# LHR_Mag_Sensor_Mk2.net
KiCad netlist of a schematic drawn in EAGLE
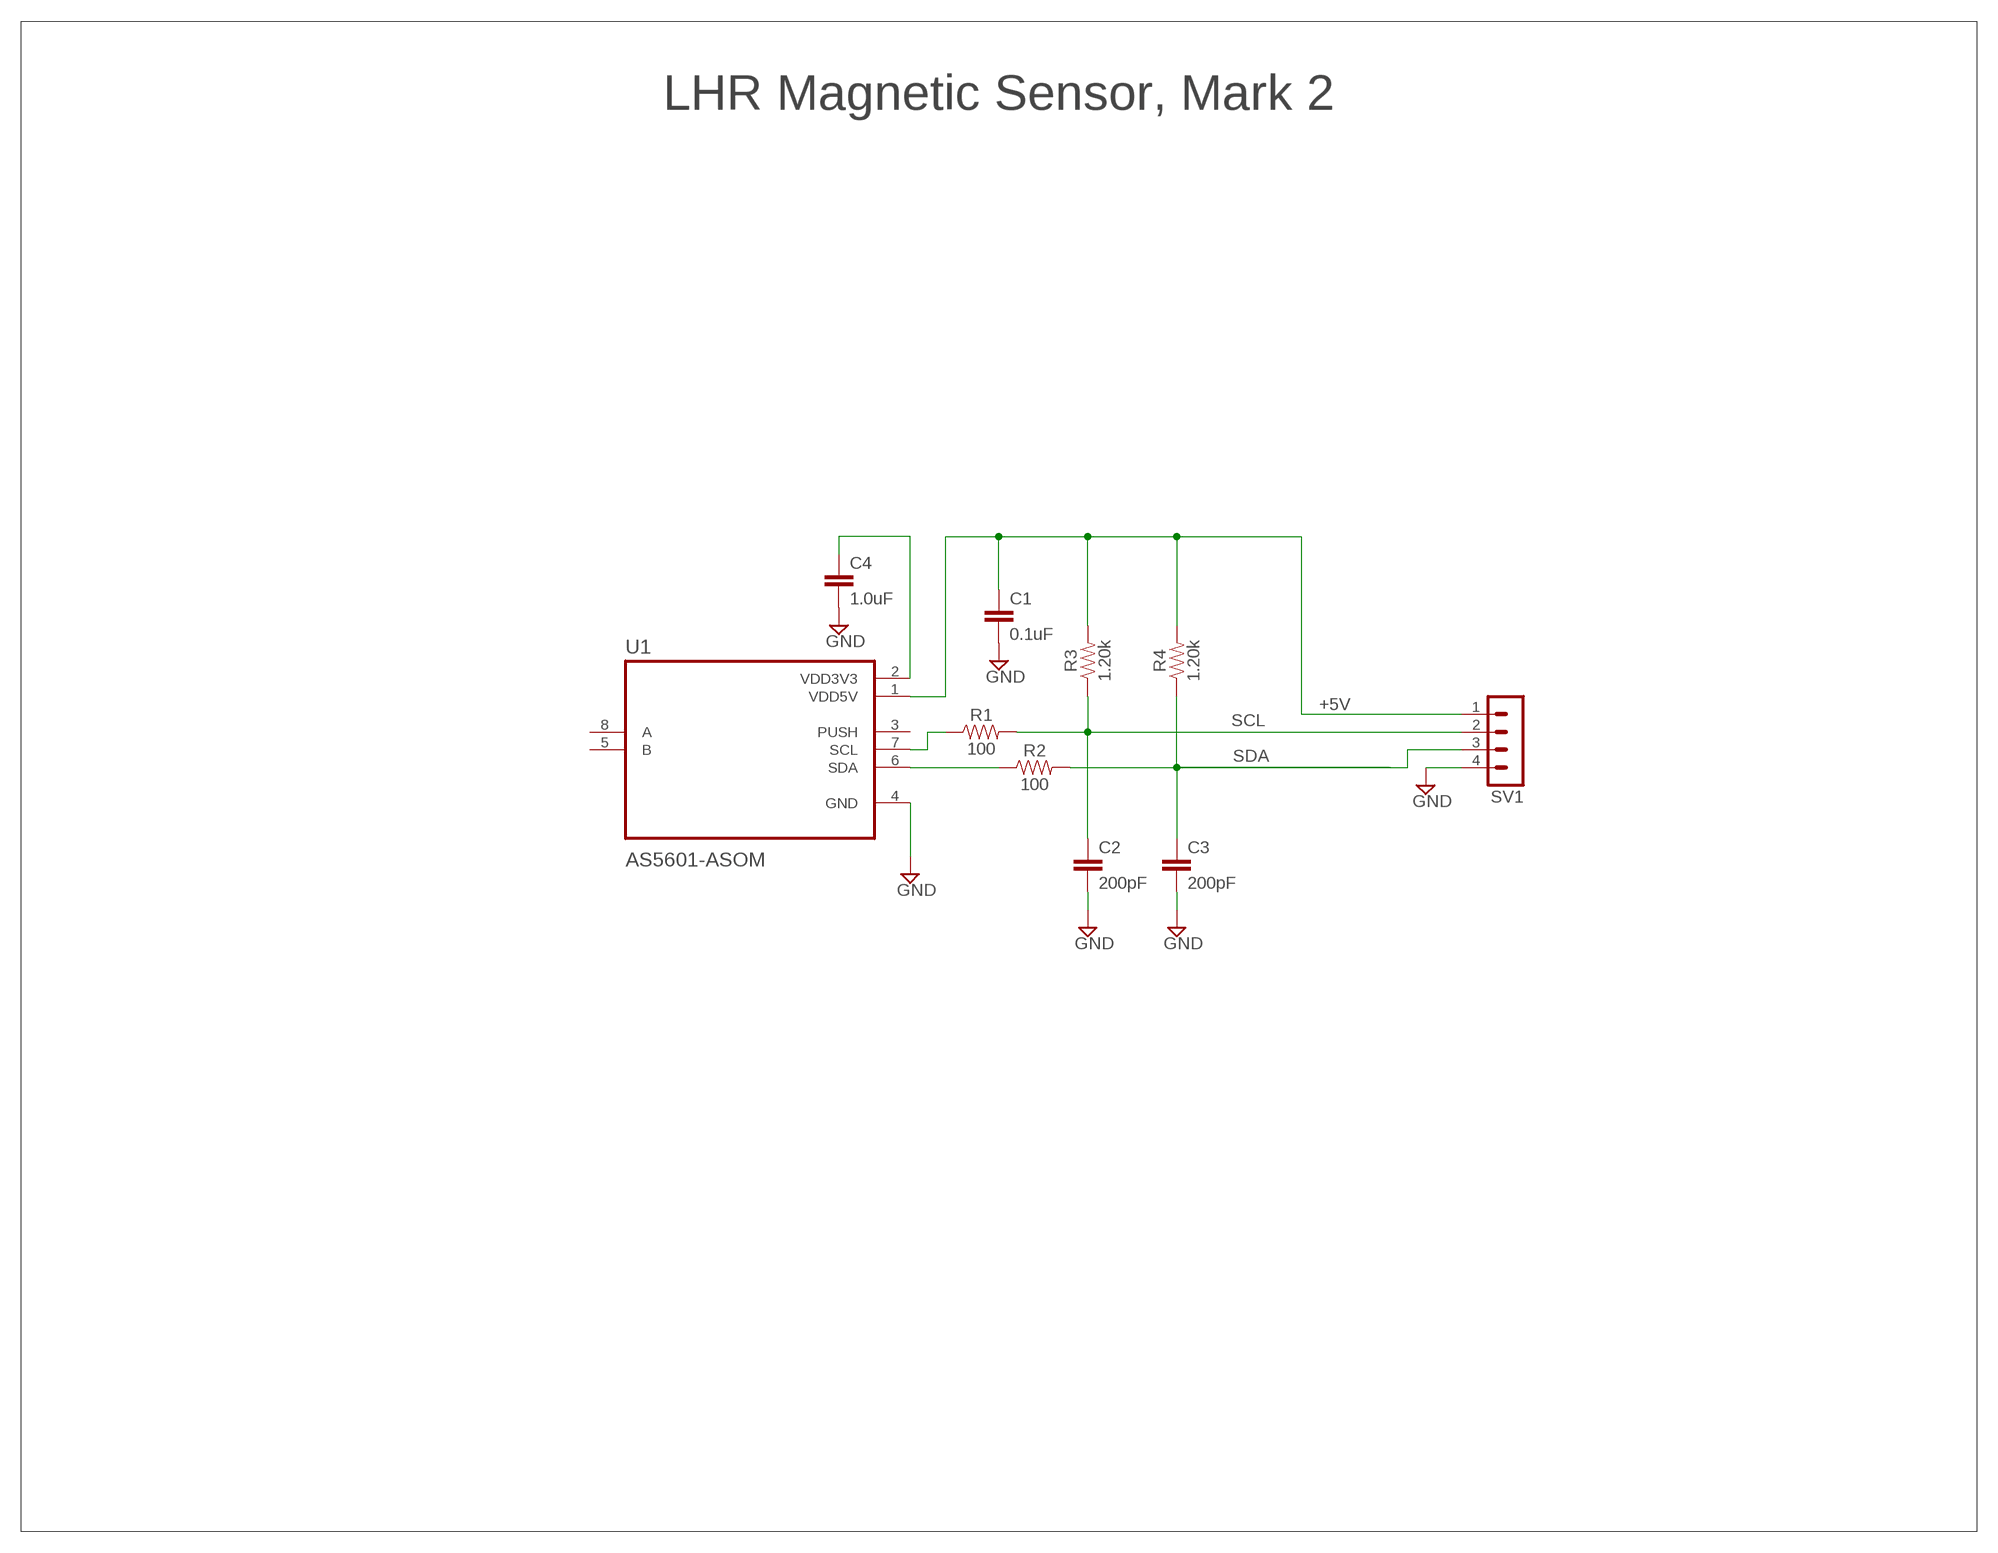
[diagram p0: schematic, sheet 1]

(export (version "E")
  (design (tool "Eeschema 10.0.6"))
  (components
    (comp (ref "C1")
      (value "0.1uF")
      (footprint "eagle-import:0603")
      (libsource (lib "eagle-import") (part "22PF-0603-50V-5%"))
    )
    (comp (ref "C2")
      (value "200pF")
      (footprint "eagle-import:0603")
      (libsource (lib "eagle-import") (part "22PF-0603-50V-5%"))
    )
    (comp (ref "C3")
      (value "200pF")
      (footprint "eagle-import:0603")
      (libsource (lib "eagle-import") (part "22PF-0603-50V-5%"))
    )
    (comp (ref "C4")
      (value "1.0uF")
      (footprint "eagle-import:0603")
      (libsource (lib "eagle-import") (part "22PF-0603-50V-5%"))
    )
    (comp (ref "R1")
      (value "100")
      (footprint "eagle-import:0603")
      (libsource (lib "eagle-import") (part "10KOHM-0603-1/10W-1%"))
    )
    (comp (ref "R2")
      (value "100")
      (footprint "eagle-import:0603")
      (libsource (lib "eagle-import") (part "10KOHM-0603-1/10W-1%"))
    )
    (comp (ref "R3")
      (value "1.20k")
      (footprint "eagle-import:0603")
      (libsource (lib "eagle-import") (part "1.20KOHM-0603-1/10W-1%"))
    )
    (comp (ref "R4")
      (value "1.20k")
      (footprint "eagle-import:0603")
      (libsource (lib "eagle-import") (part "1.20KOHM-0603-1/10W-1%"))
    )
    (comp (ref "SV1")
      (value "MA04-1")
      (footprint "eagle-import:MA04-1")
      (libsource (lib "eagle-import") (part "MA04-1"))
    )
    (comp (ref "U1")
      (value "AS5601-ASOM")
      (footprint "eagle-import:SOIC127P600X172-8N")
      (fields (field (name "MF") "ams"))
      (libsource (lib "eagle-import") (part "AS5601-ASOM"))
    )
  )
  (nets
    (net (code "1") (name "/+5V") (class "Default")
      (node (ref "C1") (pin "1") (pinfunction "1_1") (pintype "passive"))
      (node (ref "R3") (pin "2") (pinfunction "2_2") (pintype "passive"))
      (node (ref "R4") (pin "2") (pinfunction "2_2") (pintype "passive"))
      (node (ref "SV1") (pin "1") (pinfunction "1_1") (pintype "passive"))
      (node (ref "U1") (pin "1") (pinfunction "VDD5V_1") (pintype "power_in"))
    )
    (net (code "2") (name "/SCL") (class "Default")
      (node (ref "C2") (pin "1") (pinfunction "1_1") (pintype "passive"))
      (node (ref "R1") (pin "2") (pinfunction "2_2") (pintype "passive"))
      (node (ref "R3") (pin "1") (pinfunction "1_1") (pintype "passive"))
      (node (ref "SV1") (pin "2") (pinfunction "2_2") (pintype "passive"))
    )
    (net (code "3") (name "/SDA") (class "Default")
      (node (ref "C3") (pin "1") (pinfunction "1_1") (pintype "passive"))
      (node (ref "R2") (pin "2") (pinfunction "2_2") (pintype "passive"))
      (node (ref "R4") (pin "1") (pinfunction "1_1") (pintype "passive"))
      (node (ref "SV1") (pin "3") (pinfunction "3_3") (pintype "passive"))
    )
    (net (code "4") (name "GND") (class "Default")
      (node (ref "C1") (pin "2") (pinfunction "2_2") (pintype "passive"))
      (node (ref "C2") (pin "2") (pinfunction "2_2") (pintype "passive"))
      (node (ref "C3") (pin "2") (pinfunction "2_2") (pintype "passive"))
      (node (ref "C4") (pin "2") (pinfunction "2_2") (pintype "passive"))
      (node (ref "SV1") (pin "4") (pinfunction "4_4") (pintype "passive"))
      (node (ref "U1") (pin "4") (pinfunction "GND_4") (pintype "power_in"))
    )
    (net (code "5") (name "Net-(U1-SCL)") (class "Default")
      (node (ref "R1") (pin "1") (pinfunction "1_1") (pintype "passive"))
      (node (ref "U1") (pin "7") (pinfunction "SCL_7") (pintype "bidirectional"))
    )
    (net (code "6") (name "Net-(U1-SDA)") (class "Default")
      (node (ref "R2") (pin "1") (pinfunction "1_1") (pintype "passive"))
      (node (ref "U1") (pin "6") (pinfunction "SDA_6") (pintype "bidirectional"))
    )
    (net (code "7") (name "Net-(U1-VDD3V3)") (class "Default")
      (node (ref "C4") (pin "1") (pinfunction "1_1") (pintype "passive"))
      (node (ref "U1") (pin "2") (pinfunction "VDD3V3_2") (pintype "power_in"))
    )
    (net (code "8") (name "unconnected-(U1-A-Pad8)") (class "Default")
      (node (ref "U1") (pin "8") (pinfunction "A_8") (pintype "bidirectional"))
    )
    (net (code "9") (name "unconnected-(U1-B-Pad5)") (class "Default")
      (node (ref "U1") (pin "5") (pinfunction "B_5") (pintype "bidirectional"))
    )
    (net (code "10") (name "unconnected-(U1-PUSH-Pad3)") (class "Default")
      (node (ref "U1") (pin "3") (pinfunction "PUSH_3") (pintype "bidirectional"))
    )
  )
)
